# hat.net
KiCad netlist of a schematic drawn in EAGLE
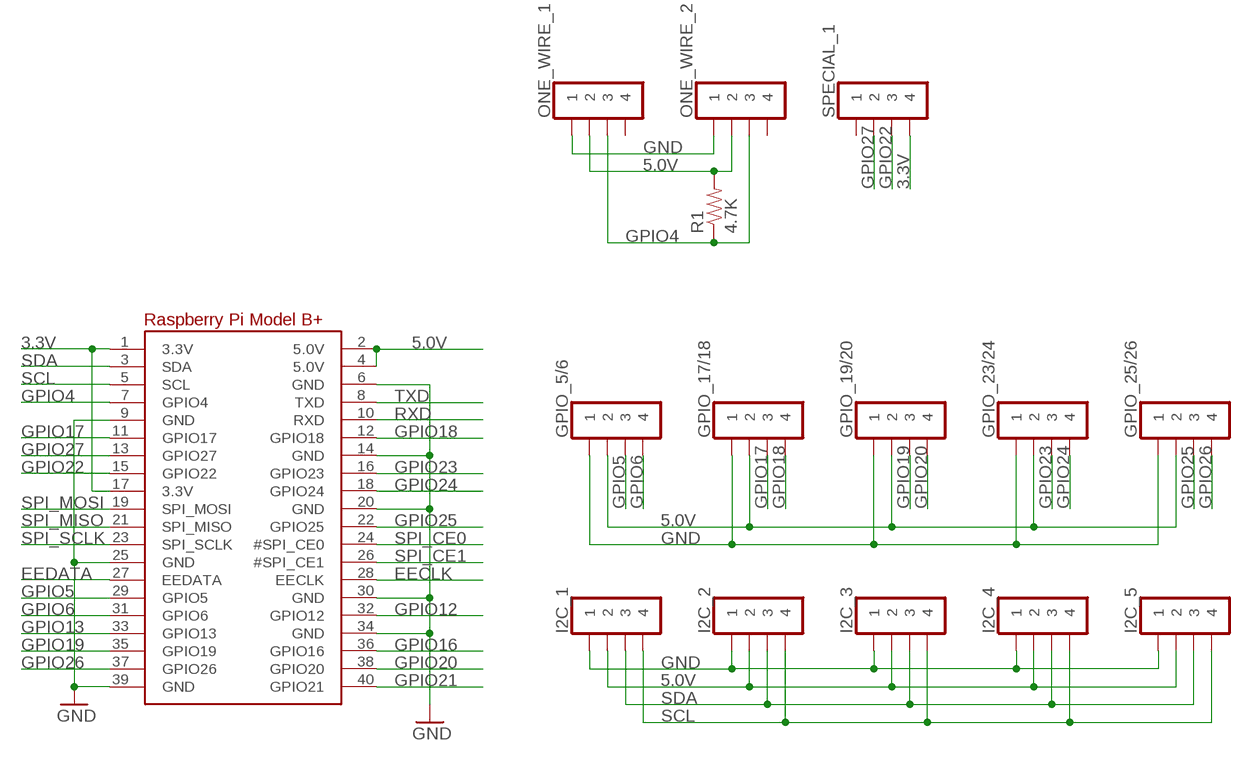
[diagram p0: schematic, sheet 1]

(export (version "E")
  (design (tool "Eeschema 10.0.6"))
  (components
    (comp (ref "GPIO_5/6")
      (value "MOLEX_0705430003")
      (footprint "eagle-import:MOLEX_0705430003")
      (libsource (lib "eagle-import") (part "MOLEX_0705430003"))
    )
    (comp (ref "GPIO_17/18")
      (value "MOLEX_0705430003")
      (footprint "eagle-import:MOLEX_0705430003")
      (libsource (lib "eagle-import") (part "MOLEX_0705430003"))
    )
    (comp (ref "GPIO_19/20")
      (value "MOLEX_0705430003")
      (footprint "eagle-import:MOLEX_0705430003")
      (libsource (lib "eagle-import") (part "MOLEX_0705430003"))
    )
    (comp (ref "GPIO_23/24")
      (value "MOLEX_0705430003")
      (footprint "eagle-import:MOLEX_0705430003")
      (libsource (lib "eagle-import") (part "MOLEX_0705430003"))
    )
    (comp (ref "GPIO_25/26")
      (value "MOLEX_0705430003")
      (footprint "eagle-import:MOLEX_0705430003")
      (libsource (lib "eagle-import") (part "MOLEX_0705430003"))
    )
    (comp (ref "I2C_1")
      (value "MOLEX_0705430003")
      (footprint "eagle-import:MOLEX_0705430003")
      (libsource (lib "eagle-import") (part "MOLEX_0705430003"))
    )
    (comp (ref "I2C_2")
      (value "MOLEX_0705430003")
      (footprint "eagle-import:MOLEX_0705430003")
      (libsource (lib "eagle-import") (part "MOLEX_0705430003"))
    )
    (comp (ref "I2C_3")
      (value "MOLEX_0705430003")
      (footprint "eagle-import:MOLEX_0705430003")
      (libsource (lib "eagle-import") (part "MOLEX_0705430003"))
    )
    (comp (ref "I2C_4")
      (value "MOLEX_0705430003")
      (footprint "eagle-import:MOLEX_0705430003")
      (libsource (lib "eagle-import") (part "MOLEX_0705430003"))
    )
    (comp (ref "I2C_5")
      (value "MOLEX_0705430003")
      (footprint "eagle-import:MOLEX_0705430003")
      (libsource (lib "eagle-import") (part "MOLEX_0705430003"))
    )
    (comp (ref "ONE_WIRE_1")
      (value "MOLEX_0705430003")
      (footprint "eagle-import:MOLEX_0705430003")
      (libsource (lib "eagle-import") (part "MOLEX_0705430003"))
    )
    (comp (ref "ONE_WIRE_2")
      (value "MOLEX_0705430003")
      (footprint "eagle-import:MOLEX_0705430003")
      (libsource (lib "eagle-import") (part "MOLEX_0705430003"))
    )
    (comp (ref "R1")
      (value "4.7K")
      (footprint "eagle-import:AXIAL-0.3")
      (libsource (lib "eagle-import") (part "RESISTORPTH1"))
    )
    (comp (ref "RPI1")
      (value "RASPBERRYPI_BPLUS_HATNOSLOTS")
      (footprint "eagle-import:PI_HAT_NOSLOTS")
      (libsource (lib "eagle-import") (part "RASPBERRYPI_BPLUS_HATNOSLOTS"))
    )
    (comp (ref "SPECIAL_1")
      (value "MOLEX_0705430003")
      (footprint "eagle-import:MOLEX_0705430003")
      (libsource (lib "eagle-import") (part "MOLEX_0705430003"))
    )
  )
  (nets
    (net (code "1") (name "/3.3V") (class "Default")
      (node (ref "RPI1") (pin "1") (pinfunction "3.3V_1") (pintype "power_in"))
      (node (ref "RPI1") (pin "17") (pinfunction "3.3V_17") (pintype "power_in"))
      (node (ref "SPECIAL_1") (pin "4") (pinfunction "4_4") (pintype "passive"))
    )
    (net (code "2") (name "/5.0V") (class "Default")
      (node (ref "GPIO_17/18") (pin "2") (pinfunction "2_2") (pintype "passive"))
      (node (ref "GPIO_19/20") (pin "2") (pinfunction "2_2") (pintype "passive"))
      (node (ref "GPIO_23/24") (pin "2") (pinfunction "2_2") (pintype "passive"))
      (node (ref "GPIO_25/26") (pin "2") (pinfunction "2_2") (pintype "passive"))
      (node (ref "GPIO_5/6") (pin "2") (pinfunction "2_2") (pintype "passive"))
      (node (ref "I2C_1") (pin "2") (pinfunction "2_2") (pintype "passive"))
      (node (ref "I2C_2") (pin "2") (pinfunction "2_2") (pintype "passive"))
      (node (ref "I2C_3") (pin "2") (pinfunction "2_2") (pintype "passive"))
      (node (ref "I2C_4") (pin "2") (pinfunction "2_2") (pintype "passive"))
      (node (ref "I2C_5") (pin "2") (pinfunction "2_2") (pintype "passive"))
      (node (ref "ONE_WIRE_1") (pin "2") (pinfunction "2_2") (pintype "passive"))
      (node (ref "ONE_WIRE_2") (pin "2") (pinfunction "2_2") (pintype "passive"))
      (node (ref "R1") (pin "P$2") (pinfunction "2_P$2") (pintype "passive"))
      (node (ref "RPI1") (pin "2") (pinfunction "5.0V_2") (pintype "power_in"))
      (node (ref "RPI1") (pin "4") (pinfunction "5.0V_4") (pintype "power_in"))
    )
    (net (code "3") (name "/EECLK") (class "Default")
      (node (ref "RPI1") (pin "28") (pinfunction "EECLK_28") (pintype "power_in"))
    )
    (net (code "4") (name "/EEDATA") (class "Default")
      (node (ref "RPI1") (pin "27") (pinfunction "EEDATA_27") (pintype "bidirectional"))
    )
    (net (code "5") (name "/GPIO4") (class "Default")
      (node (ref "ONE_WIRE_1") (pin "3") (pinfunction "3_3") (pintype "passive"))
      (node (ref "ONE_WIRE_2") (pin "3") (pinfunction "3_3") (pintype "passive"))
      (node (ref "R1") (pin "P$1") (pinfunction "1_P$1") (pintype "passive"))
      (node (ref "RPI1") (pin "7") (pinfunction "GPIO4_7") (pintype "bidirectional"))
    )
    (net (code "6") (name "/GPIO5") (class "Default")
      (node (ref "GPIO_5/6") (pin "3") (pinfunction "3_3") (pintype "passive"))
      (node (ref "RPI1") (pin "29") (pinfunction "GPIO5_29") (pintype "bidirectional"))
    )
    (net (code "7") (name "/GPIO6") (class "Default")
      (node (ref "GPIO_5/6") (pin "4") (pinfunction "4_4") (pintype "passive"))
      (node (ref "RPI1") (pin "31") (pinfunction "GPIO6_31") (pintype "power_in"))
    )
    (net (code "8") (name "/GPIO12") (class "Default")
      (node (ref "RPI1") (pin "32") (pinfunction "GPIO12_32") (pintype "bidirectional"))
    )
    (net (code "9") (name "/GPIO13") (class "Default")
      (node (ref "RPI1") (pin "33") (pinfunction "GPIO13_33") (pintype "bidirectional"))
    )
    (net (code "10") (name "/GPIO16") (class "Default")
      (node (ref "RPI1") (pin "36") (pinfunction "GPIO16_36") (pintype "power_in"))
    )
    (net (code "11") (name "/GPIO17") (class "Default")
      (node (ref "GPIO_17/18") (pin "3") (pinfunction "3_3") (pintype "passive"))
      (node (ref "RPI1") (pin "11") (pinfunction "GPIO17_11") (pintype "bidirectional"))
    )
    (net (code "12") (name "/GPIO18") (class "Default")
      (node (ref "GPIO_17/18") (pin "4") (pinfunction "4_4") (pintype "passive"))
      (node (ref "RPI1") (pin "12") (pinfunction "GPIO18_12") (pintype "bidirectional"))
    )
    (net (code "13") (name "/GPIO19") (class "Default")
      (node (ref "GPIO_19/20") (pin "3") (pinfunction "3_3") (pintype "passive"))
      (node (ref "RPI1") (pin "35") (pinfunction "GPIO19_35") (pintype "bidirectional"))
    )
    (net (code "14") (name "/GPIO20") (class "Default")
      (node (ref "GPIO_19/20") (pin "4") (pinfunction "4_4") (pintype "passive"))
      (node (ref "RPI1") (pin "38") (pinfunction "GPIO20_38") (pintype "bidirectional"))
    )
    (net (code "15") (name "/GPIO21") (class "Default")
      (node (ref "RPI1") (pin "40") (pinfunction "GPIO21_40") (pintype "bidirectional"))
    )
    (net (code "16") (name "/GPIO22") (class "Default")
      (node (ref "RPI1") (pin "15") (pinfunction "GPIO22_15") (pintype "bidirectional"))
      (node (ref "SPECIAL_1") (pin "3") (pinfunction "3_3") (pintype "passive"))
    )
    (net (code "17") (name "/GPIO23") (class "Default")
      (node (ref "GPIO_23/24") (pin "3") (pinfunction "3_3") (pintype "passive"))
      (node (ref "RPI1") (pin "16") (pinfunction "GPIO23_16") (pintype "bidirectional"))
    )
    (net (code "18") (name "/GPIO24") (class "Default")
      (node (ref "GPIO_23/24") (pin "4") (pinfunction "4_4") (pintype "passive"))
      (node (ref "RPI1") (pin "18") (pinfunction "GPIO24_18") (pintype "bidirectional"))
    )
    (net (code "19") (name "/GPIO25") (class "Default")
      (node (ref "GPIO_25/26") (pin "3") (pinfunction "3_3") (pintype "passive"))
      (node (ref "RPI1") (pin "22") (pinfunction "GPIO25_22") (pintype "bidirectional"))
    )
    (net (code "20") (name "/GPIO26") (class "Default")
      (node (ref "GPIO_25/26") (pin "4") (pinfunction "4_4") (pintype "passive"))
      (node (ref "RPI1") (pin "37") (pinfunction "GPIO26_37") (pintype "bidirectional"))
    )
    (net (code "21") (name "/GPIO27") (class "Default")
      (node (ref "RPI1") (pin "13") (pinfunction "GPIO27_13") (pintype "bidirectional"))
      (node (ref "SPECIAL_1") (pin "2") (pinfunction "2_2") (pintype "passive"))
    )
    (net (code "22") (name "/RXD") (class "Default")
      (node (ref "RPI1") (pin "10") (pinfunction "RXD_10") (pintype "bidirectional"))
    )
    (net (code "23") (name "/SCL") (class "Default")
      (node (ref "I2C_1") (pin "4") (pinfunction "4_4") (pintype "passive"))
      (node (ref "I2C_2") (pin "4") (pinfunction "4_4") (pintype "passive"))
      (node (ref "I2C_3") (pin "4") (pinfunction "4_4") (pintype "passive"))
      (node (ref "I2C_4") (pin "4") (pinfunction "4_4") (pintype "passive"))
      (node (ref "I2C_5") (pin "4") (pinfunction "4_4") (pintype "passive"))
      (node (ref "RPI1") (pin "5") (pinfunction "SCL_5") (pintype "bidirectional"))
    )
    (net (code "24") (name "/SDA") (class "Default")
      (node (ref "I2C_1") (pin "3") (pinfunction "3_3") (pintype "passive"))
      (node (ref "I2C_2") (pin "3") (pinfunction "3_3") (pintype "passive"))
      (node (ref "I2C_3") (pin "3") (pinfunction "3_3") (pintype "passive"))
      (node (ref "I2C_4") (pin "3") (pinfunction "3_3") (pintype "passive"))
      (node (ref "I2C_5") (pin "3") (pinfunction "3_3") (pintype "passive"))
      (node (ref "RPI1") (pin "3") (pinfunction "SDA_3") (pintype "bidirectional"))
    )
    (net (code "25") (name "/SPI_CE0") (class "Default")
      (node (ref "RPI1") (pin "24") (pinfunction "#SPI_CE0_24") (pintype "bidirectional"))
    )
    (net (code "26") (name "/SPI_CE1") (class "Default")
      (node (ref "RPI1") (pin "26") (pinfunction "#SPI_CE1_26") (pintype "bidirectional"))
    )
    (net (code "27") (name "/SPI_MISO") (class "Default")
      (node (ref "RPI1") (pin "21") (pinfunction "SPI_MISO_21") (pintype "bidirectional"))
    )
    (net (code "28") (name "/SPI_MOSI") (class "Default")
      (node (ref "RPI1") (pin "19") (pinfunction "SPI_MOSI_19") (pintype "bidirectional"))
    )
    (net (code "29") (name "/SPI_SCLK") (class "Default")
      (node (ref "RPI1") (pin "23") (pinfunction "SPI_SCLK_23") (pintype "bidirectional"))
    )
    (net (code "30") (name "/TXD") (class "Default")
      (node (ref "RPI1") (pin "8") (pinfunction "TXD_8") (pintype "output"))
    )
    (net (code "31") (name "GND") (class "Default")
      (node (ref "GPIO_17/18") (pin "1") (pinfunction "1_1") (pintype "passive"))
      (node (ref "GPIO_19/20") (pin "1") (pinfunction "1_1") (pintype "passive"))
      (node (ref "GPIO_23/24") (pin "1") (pinfunction "1_1") (pintype "passive"))
      (node (ref "GPIO_25/26") (pin "1") (pinfunction "1_1") (pintype "passive"))
      (node (ref "GPIO_5/6") (pin "1") (pinfunction "1_1") (pintype "passive"))
      (node (ref "I2C_1") (pin "1") (pinfunction "1_1") (pintype "passive"))
      (node (ref "I2C_2") (pin "1") (pinfunction "1_1") (pintype "passive"))
      (node (ref "I2C_3") (pin "1") (pinfunction "1_1") (pintype "passive"))
      (node (ref "I2C_4") (pin "1") (pinfunction "1_1") (pintype "passive"))
      (node (ref "I2C_5") (pin "1") (pinfunction "1_1") (pintype "passive"))
      (node (ref "ONE_WIRE_1") (pin "1") (pinfunction "1_1") (pintype "passive"))
      (node (ref "ONE_WIRE_2") (pin "1") (pinfunction "1_1") (pintype "passive"))
      (node (ref "RPI1") (pin "14") (pinfunction "GND_14") (pintype "power_in"))
      (node (ref "RPI1") (pin "20") (pinfunction "GND_20") (pintype "power_in"))
      (node (ref "RPI1") (pin "25") (pinfunction "GND_25") (pintype "power_in"))
      (node (ref "RPI1") (pin "30") (pinfunction "GND_30") (pintype "bidirectional"))
      (node (ref "RPI1") (pin "34") (pinfunction "GND_34") (pintype "bidirectional"))
      (node (ref "RPI1") (pin "39") (pinfunction "GND_39") (pintype "power_in"))
      (node (ref "RPI1") (pin "6") (pinfunction "GND_6") (pintype "power_in"))
      (node (ref "RPI1") (pin "9") (pinfunction "GND_9") (pintype "power_in"))
    )
    (net (code "32") (name "unconnected-(ONE_WIRE_1-Pad4)") (class "Default")
      (node (ref "ONE_WIRE_1") (pin "4") (pinfunction "4_4") (pintype "passive"))
    )
    (net (code "33") (name "unconnected-(ONE_WIRE_2-Pad4)") (class "Default")
      (node (ref "ONE_WIRE_2") (pin "4") (pinfunction "4_4") (pintype "passive"))
    )
    (net (code "34") (name "unconnected-(SPECIAL_1-Pad1)") (class "Default")
      (node (ref "SPECIAL_1") (pin "1") (pinfunction "1_1") (pintype "passive"))
    )
  )
)
